# Prototype_V1.net
KiCad netlist of a schematic drawn in Altium Designer
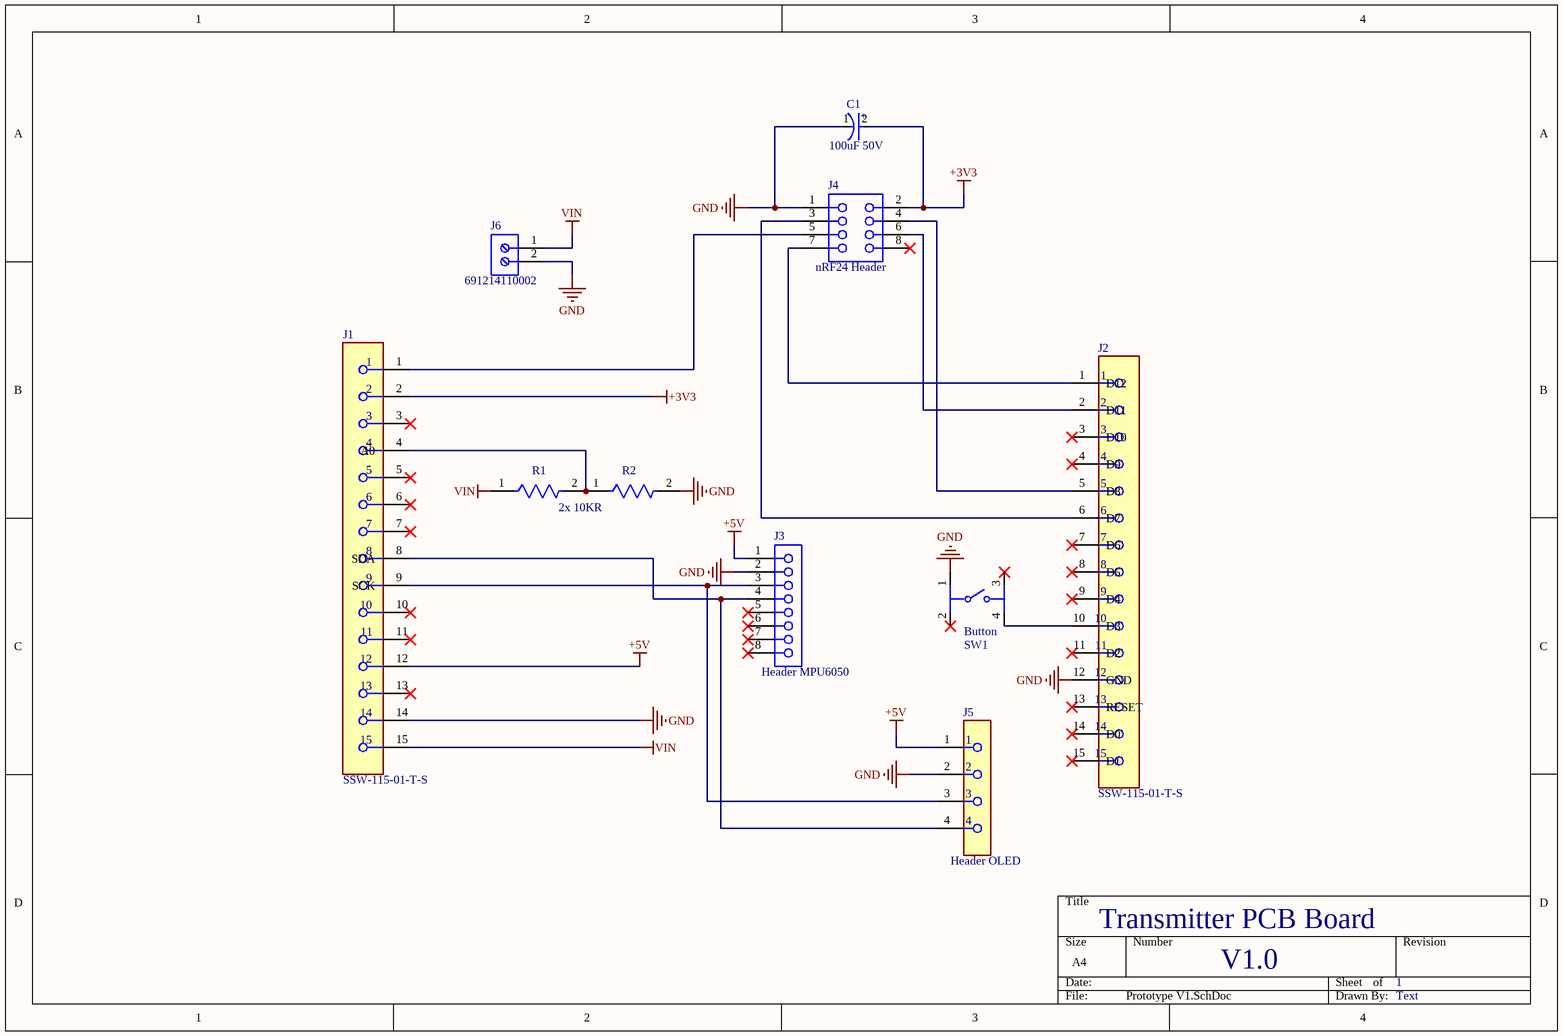
[diagram p0: Prototype V1.SchDoc]

(export (version "E")
  (design (tool "Eeschema 10.0.6"))
  (components
    (comp (ref "C1")
      (value "100uF 50V")
      (footprint "FP-EEU-FR1H101B-MFG")
      (description "CAP ALUM 100UF 20% 50V RADIAL")
      (fields (field (name "TOLERANCE") "20%"))
      (libsource (lib "Altium Content Vault") (part "cf48714ba7e38822c1575c7ec0b6d1f"))
    )
    (comp (ref "J1")
      (value "SSW-115-01-T-S")
      (footprint "FP-SSW-115-01-T-S-MFG")
      (description "CONN RCPT 15POS 0.1 TIN PCB")
      (libsource (lib "") (part "de2cdd76613f87adcba81301aaab7e9_1"))
    )
    (comp (ref "J2")
      (value "SSW-115-01-T-S")
      (footprint "FP-SSW-115-01-T-S-MFG")
      (description "CONN RCPT 15POS 0.1 TIN PCB")
      (libsource (lib "Altium Content Vault") (part "de2cdd76613f87adcba81301aaab7e9"))
    )
    (comp (ref "J3")
      (value "Header MPU6050")
      (footprint "61300811821")
      (libsource (lib "Altium Content Vault") (part "Header_Female_1R_08P"))
    )
    (comp (ref "J4")
      (value "nRF24 Header")
      (footprint "61300821821")
      (libsource (lib "Altium Content Vault") (part "Header_Female_2R_08P"))
    )
    (comp (ref "J5")
      (value "Header OLED")
      (footprint "FP-SSW-104-02-G-S-MFG")
      (libsource (lib "Altium Content Vault") (part "56792406a6bd5c25e158f553ecd1aa7"))
    )
    (comp (ref "J6")
      (value "691214110002")
      (footprint "691214110002")
      (fields (field (name "VOLTAGE") "300V"))
      (libsource (lib "Altium Content Vault") (part "TBL - 1R - 02P - Screw"))
    )
    (comp (ref "R1")
      (value "~")
      (footprint "FP-ZOR-25-R-52-0R-MFG")
      (description "RES 0 OHM JUMPER 1/4W AXIAL")
      (fields (field (name "TOLERANCE") "5%"))
      (libsource (lib "Altium Content Vault") (part "d029466b076adaef5daba0b7f088f1c"))
    )
    (comp (ref "R2")
      (value "2x 10KR")
      (footprint "FP-ZOR-25-R-52-0R-MFG")
      (description "RES 0 OHM JUMPER 1/4W AXIAL")
      (fields (field (name "TOLERANCE") "5%"))
      (libsource (lib "Altium Content Vault") (part "d029466b076adaef5daba0b7f088f1c"))
    )
    (comp (ref "SW1")
      (value "Button")
      (footprint "FP-2-1825910-7-MFG")
      (description "SWITCH TACTILE SPST-NO 0.05A 24V")
      (fields
        (field (name "MANUFACTURER PART NUMBER") "2-1825910-7")
        (field (name "MANUFACTURER") "TE Connectivity")
      )
      (libsource (lib "Altium Content Vault") (part "b8895f3f4cefb76e1819d2863dba89b"))
    )
  )
  (nets
    (net (code "1") (name "+3V3") (class "Default")
      (node (ref "C1") (pin "2") (pinfunction "A_2") (pintype "passive"))
      (node (ref "J1") (pin "2") (pinfunction "2_2") (pintype "passive"))
      (node (ref "J4") (pin "2") (pinfunction "2_2") (pintype "passive"))
    )
    (net (code "2") (name "+5V") (class "Default")
      (node (ref "J1") (pin "12") (pinfunction "12_12") (pintype "passive"))
      (node (ref "J3") (pin "1") (pinfunction "1_1") (pintype "passive"))
      (node (ref "J5") (pin "1") (pinfunction "1_1") (pintype "passive"))
    )
    (net (code "3") (name "GND") (class "Default")
      (node (ref "C1") (pin "1") (pinfunction "C_1") (pintype "passive"))
      (node (ref "J1") (pin "14") (pinfunction "14_14") (pintype "passive"))
      (node (ref "J2") (pin "12") (pinfunction "GND_12") (pintype "passive"))
      (node (ref "J3") (pin "2") (pinfunction "2_2") (pintype "passive"))
      (node (ref "J4") (pin "1") (pinfunction "1_1") (pintype "passive"))
      (node (ref "J5") (pin "2") (pinfunction "2_2") (pintype "passive"))
      (node (ref "J6") (pin "2") (pinfunction "2_2") (pintype "passive"))
      (node (ref "R2") (pin "2") (pinfunction "2_2") (pintype "passive"))
      (node (ref "SW1") (pin "1") (pinfunction "1_1") (pintype "passive"))
    )
    (net (code "4") (name "Net-(J1-A0)") (class "Default")
      (node (ref "J1") (pin "4") (pinfunction "A0_4") (pintype "passive"))
      (node (ref "R1") (pin "2") (pinfunction "2_2") (pintype "passive"))
      (node (ref "R2") (pin "1") (pinfunction "1_1") (pintype "passive"))
    )
    (net (code "5") (name "Net-(J1-Pad1)") (class "Default")
      (node (ref "J1") (pin "1") (pinfunction "1_1") (pintype "passive"))
      (node (ref "J4") (pin "5") (pinfunction "5_5") (pintype "passive"))
    )
    (net (code "6") (name "Net-(J1-SCK)") (class "Default")
      (node (ref "J1") (pin "9") (pinfunction "SCK_9") (pintype "passive"))
      (node (ref "J3") (pin "3") (pinfunction "3_3") (pintype "passive"))
      (node (ref "J5") (pin "3") (pinfunction "3_3") (pintype "passive"))
    )
    (net (code "7") (name "Net-(J1-SDA)") (class "Default")
      (node (ref "J1") (pin "8") (pinfunction "SDA_8") (pintype "passive"))
      (node (ref "J3") (pin "4") (pinfunction "4_4") (pintype "passive"))
      (node (ref "J5") (pin "4") (pinfunction "4_4") (pintype "passive"))
    )
    (net (code "8") (name "Net-(J2-D3)") (class "Default")
      (node (ref "J2") (pin "10") (pinfunction "D3_10") (pintype "passive"))
      (node (ref "SW1") (pin "4") (pinfunction "4_4") (pintype "passive"))
    )
    (net (code "9") (name "Net-(J2-D7)") (class "Default")
      (node (ref "J2") (pin "6") (pinfunction "D7_6") (pintype "passive"))
      (node (ref "J4") (pin "3") (pinfunction "3_3") (pintype "passive"))
    )
    (net (code "10") (name "Net-(J2-D8)") (class "Default")
      (node (ref "J2") (pin "5") (pinfunction "D8_5") (pintype "passive"))
      (node (ref "J4") (pin "4") (pinfunction "4_4") (pintype "passive"))
    )
    (net (code "11") (name "Net-(J2-D11)") (class "Default")
      (node (ref "J2") (pin "2") (pinfunction "D11_2") (pintype "passive"))
      (node (ref "J4") (pin "6") (pinfunction "6_6") (pintype "passive"))
    )
    (net (code "12") (name "Net-(J2-D12)") (class "Default")
      (node (ref "J2") (pin "1") (pinfunction "D12_1") (pintype "passive"))
      (node (ref "J4") (pin "7") (pinfunction "7_7") (pintype "passive"))
    )
    (net (code "13") (name "VIN") (class "Default")
      (node (ref "J1") (pin "15") (pinfunction "15_15") (pintype "passive"))
      (node (ref "J6") (pin "1") (pinfunction "1_1") (pintype "passive"))
      (node (ref "R1") (pin "1") (pinfunction "1_1") (pintype "passive"))
    )
    (net (code "14") (name "unconnected-(J1-Pad3)") (class "Default")
      (node (ref "J1") (pin "3") (pinfunction "3_3") (pintype "passive+no_connect"))
    )
    (net (code "15") (name "unconnected-(J1-Pad5)") (class "Default")
      (node (ref "J1") (pin "5") (pinfunction "5_5") (pintype "passive+no_connect"))
    )
    (net (code "16") (name "unconnected-(J1-Pad6)") (class "Default")
      (node (ref "J1") (pin "6") (pinfunction "6_6") (pintype "passive+no_connect"))
    )
    (net (code "17") (name "unconnected-(J1-Pad7)") (class "Default")
      (node (ref "J1") (pin "7") (pinfunction "7_7") (pintype "passive+no_connect"))
    )
    (net (code "18") (name "unconnected-(J1-Pad10)") (class "Default")
      (node (ref "J1") (pin "10") (pinfunction "10_10") (pintype "passive+no_connect"))
    )
    (net (code "19") (name "unconnected-(J1-Pad11)") (class "Default")
      (node (ref "J1") (pin "11") (pinfunction "11_11") (pintype "passive+no_connect"))
    )
    (net (code "20") (name "unconnected-(J1-Pad13)") (class "Default")
      (node (ref "J1") (pin "13") (pinfunction "13_13") (pintype "passive+no_connect"))
    )
    (net (code "21") (name "unconnected-(J2-D0-Pad14)") (class "Default")
      (node (ref "J2") (pin "14") (pinfunction "D0_14") (pintype "passive+no_connect"))
    )
    (net (code "22") (name "unconnected-(J2-D1-Pad15)") (class "Default")
      (node (ref "J2") (pin "15") (pinfunction "D1_15") (pintype "passive+no_connect"))
    )
    (net (code "23") (name "unconnected-(J2-D2-Pad11)") (class "Default")
      (node (ref "J2") (pin "11") (pinfunction "D2_11") (pintype "passive+no_connect"))
    )
    (net (code "24") (name "unconnected-(J2-D4-Pad9)") (class "Default")
      (node (ref "J2") (pin "9") (pinfunction "D4_9") (pintype "passive+no_connect"))
    )
    (net (code "25") (name "unconnected-(J2-D5-Pad8)") (class "Default")
      (node (ref "J2") (pin "8") (pinfunction "D5_8") (pintype "passive+no_connect"))
    )
    (net (code "26") (name "unconnected-(J2-D6-Pad7)") (class "Default")
      (node (ref "J2") (pin "7") (pinfunction "D6_7") (pintype "passive+no_connect"))
    )
    (net (code "27") (name "unconnected-(J2-D9-Pad4)") (class "Default")
      (node (ref "J2") (pin "4") (pinfunction "D9_4") (pintype "passive+no_connect"))
    )
    (net (code "28") (name "unconnected-(J2-D10-Pad3)") (class "Default")
      (node (ref "J2") (pin "3") (pinfunction "D10_3") (pintype "passive+no_connect"))
    )
    (net (code "29") (name "unconnected-(J2-RESET-Pad13)") (class "Default")
      (node (ref "J2") (pin "13") (pinfunction "RESET_13") (pintype "passive+no_connect"))
    )
    (net (code "30") (name "unconnected-(J3-Pad5)") (class "Default")
      (node (ref "J3") (pin "5") (pinfunction "5_5") (pintype "passive+no_connect"))
    )
    (net (code "31") (name "unconnected-(J3-Pad6)") (class "Default")
      (node (ref "J3") (pin "6") (pinfunction "6_6") (pintype "passive+no_connect"))
    )
    (net (code "32") (name "unconnected-(J3-Pad7)") (class "Default")
      (node (ref "J3") (pin "7") (pinfunction "7_7") (pintype "passive+no_connect"))
    )
    (net (code "33") (name "unconnected-(J3-Pad8)") (class "Default")
      (node (ref "J3") (pin "8") (pinfunction "8_8") (pintype "passive+no_connect"))
    )
    (net (code "34") (name "unconnected-(J4-Pad8)") (class "Default")
      (node (ref "J4") (pin "8") (pinfunction "8_8") (pintype "passive+no_connect"))
    )
    (net (code "35") (name "unconnected-(SW1-Pad2)") (class "Default")
      (node (ref "SW1") (pin "2") (pinfunction "2_2") (pintype "passive+no_connect"))
    )
    (net (code "36") (name "unconnected-(SW1-Pad3)") (class "Default")
      (node (ref "SW1") (pin "3") (pinfunction "3_3") (pintype "passive+no_connect"))
    )
  )
)
